# RF.net
KiCad netlist of a schematic drawn in Altium Designer
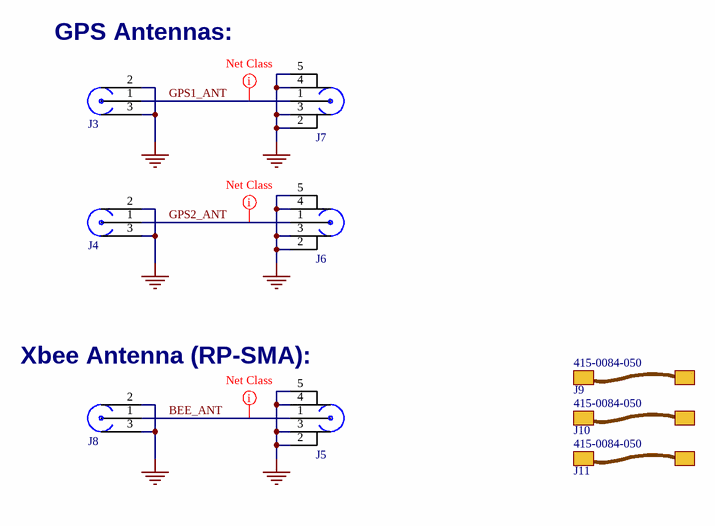
[diagram p0: RF.SchDoc]

(export (version "E")
  (design (tool "Eeschema 10.0.6"))
  (components
    (comp (ref "J3")
      (value "RF - GND x 2")
      (footprint "RF UMC SMD")
      (description "CONN UMC RCPT STR 50 OHM SMD")
      (fields
        (field (name "MANUFACTURER") "Emerson Network Power Connectivity Johnson")
        (field (name "MANUFACTURER PART NUMBER") "128-0711-201")
      )
      (libsource (lib "Connectors") (part "RF - GND x 2"))
    )
    (comp (ref "J4")
      (value "RF - GND x 2")
      (footprint "RF UMC SMD")
      (description "CONN UMC RCPT STR 50 OHM SMD")
      (fields
        (field (name "MANUFACTURER") "Emerson Network Power Connectivity Johnson")
        (field (name "MANUFACTURER PART NUMBER") "128-0711-201")
      )
      (libsource (lib "Connectors") (part "RF - GND x 2"))
    )
    (comp (ref "J5")
      (value "RF - GND x 4")
      (footprint "RF RPSMA End Launch")
      (description "CONN RPSMA JCK STR 50OHM EDGEMNT")
      (fields
        (field (name "MANUFACTURER") "Amphenol Connex")
        (field (name "MANUFACTURER PART NUMBER") "132255RP")
      )
      (libsource (lib "Connectors") (part "RF - GND x 4"))
    )
    (comp (ref "J6")
      (value "RF - GND x 4")
      (footprint "RF SMA End Launch 2")
      (description "CONN SMA RCPT STR 50OHM EDGE MNT")
      (fields (field (name "MANUFACTURER") "Molex") (field (name "MANUFACTURER PART NUMBER") "0732511150"))
      (libsource (lib "Connectors") (part "RF - GND x 4"))
    )
    (comp (ref "J7")
      (value "RF - GND x 4")
      (footprint "RF SMA End Launch 2")
      (description "CONN SMA RCPT STR 50OHM EDGE MNT")
      (fields (field (name "MANUFACTURER") "Molex") (field (name "MANUFACTURER PART NUMBER") "0732511150"))
      (libsource (lib "Connectors") (part "RF - GND x 4"))
    )
    (comp (ref "J8")
      (value "RF - GND x 2")
      (footprint "RF UMC SMD")
      (description "CONN UMC RCPT STR 50 OHM SMD")
      (fields
        (field (name "MANUFACTURER") "Emerson Network Power Connectivity Johnson")
        (field (name "MANUFACTURER PART NUMBER") "128-0711-201")
      )
      (libsource (lib "Connectors") (part "RF - GND x 2"))
    )
    (comp (ref "J9")
      (value "Cable Assembly")
      (description "CBL ASSY UMCC PLUG-PLUG 1.969\"")
      (fields
        (field (name "MANUFACTURER") "Bel Cinch")
        (field (name "MANUFACTURER PART NUMBER") "415-0084-050")
      )
      (libsource (lib "Connectors") (part "Cable Assembly"))
    )
    (comp (ref "J10")
      (value "Cable Assembly")
      (description "CBL ASSY UMCC PLUG-PLUG 1.969\"")
      (fields
        (field (name "MANUFACTURER") "Bel Cinch")
        (field (name "MANUFACTURER PART NUMBER") "415-0084-050")
      )
      (libsource (lib "Connectors") (part "Cable Assembly"))
    )
    (comp (ref "J11")
      (value "Cable Assembly")
      (description "CBL ASSY UMCC PLUG-PLUG 1.969\"")
      (fields
        (field (name "MANUFACTURER") "Bel Cinch")
        (field (name "MANUFACTURER PART NUMBER") "415-0084-050")
      )
      (libsource (lib "Connectors") (part "Cable Assembly"))
    )
  )
  (nets
    (net (code "1") (name "/BEE_ANT") (class "Default")
      (node (ref "J5") (pin "1") (pinfunction "1_1") (pintype "passive"))
      (node (ref "J8") (pin "1") (pinfunction "1_1") (pintype "passive"))
    )
    (net (code "2") (name "/GPS1_ANT") (class "Default")
      (node (ref "J3") (pin "1") (pinfunction "1_1") (pintype "passive"))
      (node (ref "J7") (pin "1") (pinfunction "1_1") (pintype "passive"))
    )
    (net (code "3") (name "/GPS2_ANT") (class "Default")
      (node (ref "J4") (pin "1") (pinfunction "1_1") (pintype "passive"))
      (node (ref "J6") (pin "1") (pinfunction "1_1") (pintype "passive"))
    )
    (net (code "4") (name "GND") (class "Default")
      (node (ref "J3") (pin "2") (pinfunction "2_2") (pintype "passive"))
      (node (ref "J3") (pin "3") (pinfunction "3_3") (pintype "passive"))
      (node (ref "J4") (pin "2") (pinfunction "2_2") (pintype "passive"))
      (node (ref "J4") (pin "3") (pinfunction "3_3") (pintype "passive"))
      (node (ref "J5") (pin "2") (pinfunction "2_2") (pintype "passive"))
      (node (ref "J5") (pin "3") (pinfunction "3_3") (pintype "passive"))
      (node (ref "J5") (pin "4") (pinfunction "4_4") (pintype "passive"))
      (node (ref "J5") (pin "5") (pinfunction "5_5") (pintype "passive"))
      (node (ref "J6") (pin "2") (pinfunction "2_2") (pintype "passive"))
      (node (ref "J6") (pin "3") (pinfunction "3_3") (pintype "passive"))
      (node (ref "J6") (pin "4") (pinfunction "4_4") (pintype "passive"))
      (node (ref "J6") (pin "5") (pinfunction "5_5") (pintype "passive"))
      (node (ref "J7") (pin "2") (pinfunction "2_2") (pintype "passive"))
      (node (ref "J7") (pin "3") (pinfunction "3_3") (pintype "passive"))
      (node (ref "J7") (pin "4") (pinfunction "4_4") (pintype "passive"))
      (node (ref "J7") (pin "5") (pinfunction "5_5") (pintype "passive"))
      (node (ref "J8") (pin "2") (pinfunction "2_2") (pintype "passive"))
      (node (ref "J8") (pin "3") (pinfunction "3_3") (pintype "passive"))
    )
  )
)
